# Order339582-10x10-SandyNoble-Polarshield.net
KiCad netlist of a schematic drawn in EAGLE
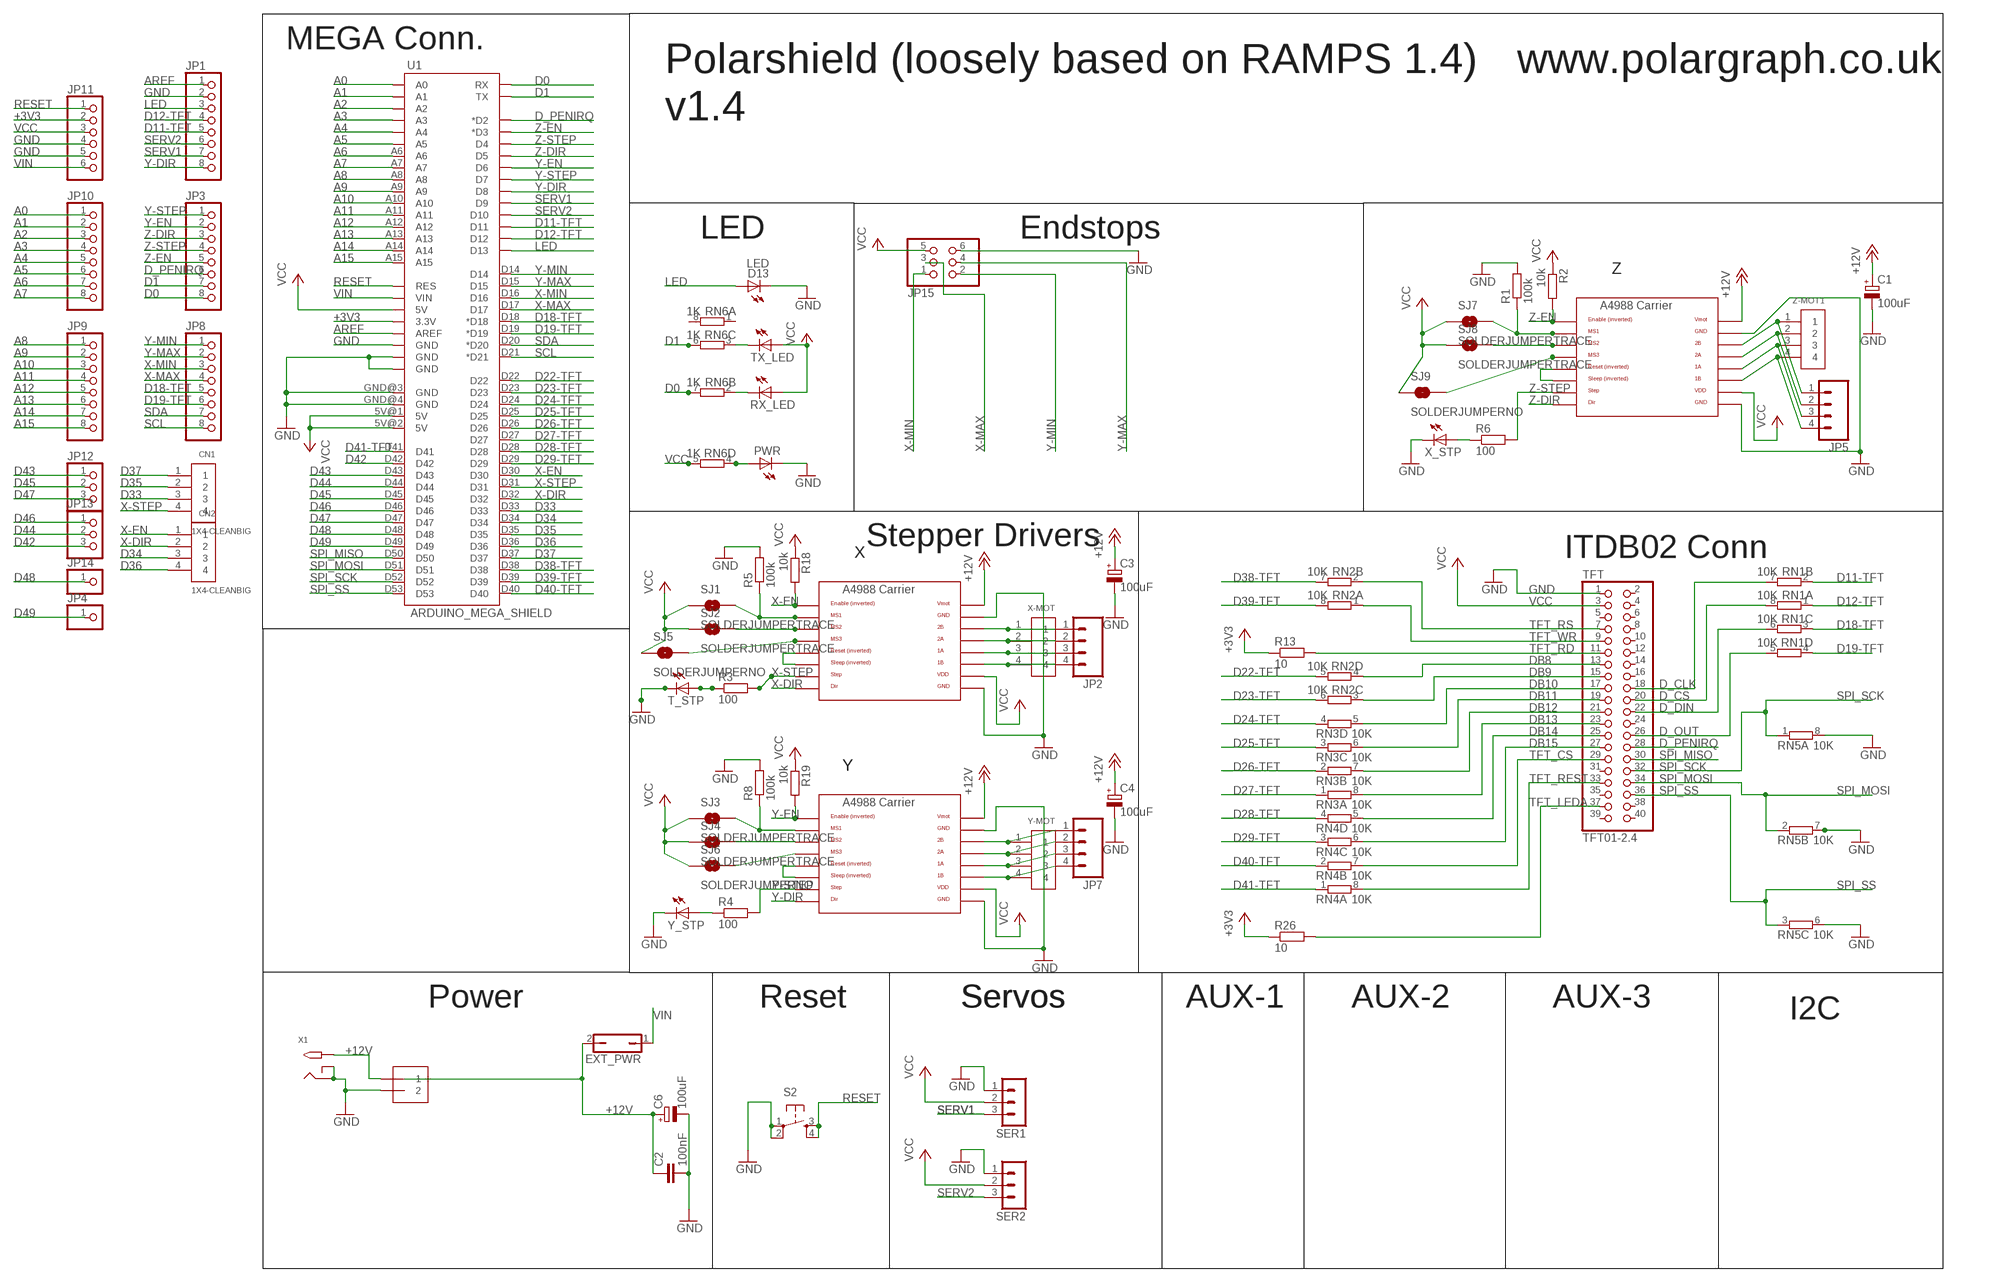
[diagram p0: schematic, sheet 1]

(export (version "E")
  (design (tool "Eeschema 10.0.6"))
  (components
    (comp (ref "C1")
      (value "100uF")
      (footprint "eagle-import:153CLV-0605")
      (libsource (lib "eagle-import") (part "CPOL-EU153CLV-0605"))
    )
    (comp (ref "C2")
      (value "100nF")
      (footprint "eagle-import:C0805")
      (libsource (lib "eagle-import") (part "C-EUC0805"))
    )
    (comp (ref "C3")
      (value "100uF")
      (footprint "eagle-import:153CLV-0605")
      (libsource (lib "eagle-import") (part "CPOL-EU153CLV-0605"))
    )
    (comp (ref "C4")
      (value "100uF")
      (footprint "eagle-import:153CLV-0605")
      (libsource (lib "eagle-import") (part "CPOL-EU153CLV-0605"))
    )
    (comp (ref "C6")
      (value "100uF")
      (footprint "eagle-import:153CLV-0605")
      (libsource (lib "eagle-import") (part "CPOL-EU153CLV-0605"))
    )
    (comp (ref "CN1")
      (value "1X4-CLEANBIG")
      (footprint "eagle-import:1X04-CLEANBIG")
      (libsource (lib "eagle-import") (part "1X4-CLEANBIG"))
    )
    (comp (ref "CN2")
      (value "1X4-CLEANBIG")
      (footprint "eagle-import:1X04-CLEANBIG")
      (libsource (lib "eagle-import") (part "1X4-CLEANBIG"))
    )
    (comp (ref "D13")
      (value "LED")
      (footprint "eagle-import:CHIP-LED0805")
      (libsource (lib "eagle-import") (part "LEDCHIP-LED0805"))
    )
    (comp (ref "EXT_PWR")
      (value "JP1Q")
      (footprint "eagle-import:JP1")
      (libsource (lib "eagle-import") (part "JP1Q"))
    )
    (comp (ref "J1")
      (value "1X2-3.5MM")
      (footprint "eagle-import:1X2-3.5MM")
      (libsource (lib "eagle-import") (part "1X2-3.5MM"))
    )
    (comp (ref "JP1")
      (value "PINHD-1X8CLEANBIG")
      (footprint "eagle-import:1X08-CLEANBIG")
      (libsource (lib "eagle-import") (part "PINHD-1X8CLEANBIG"))
    )
    (comp (ref "JP2")
      (value "M04SCREW")
      (footprint "eagle-import:SCREWTERMINAL-3.5MM-4")
      (libsource (lib "eagle-import") (part "M04SCREW"))
    )
    (comp (ref "JP3")
      (value "PINHD-1X8CLEANBIG")
      (footprint "eagle-import:1X08-CLEANBIG")
      (libsource (lib "eagle-import") (part "PINHD-1X8CLEANBIG"))
    )
    (comp (ref "JP4")
      (value "PINHD-1X1CB")
      (footprint "eagle-import:1X01-CLEANBIG")
      (libsource (lib "eagle-import") (part "PINHD-1X1CB"))
    )
    (comp (ref "JP5")
      (value "M04SCREW")
      (footprint "eagle-import:SCREWTERMINAL-3.5MM-4")
      (libsource (lib "eagle-import") (part "M04SCREW"))
    )
    (comp (ref "JP7")
      (value "M04SCREW")
      (footprint "eagle-import:SCREWTERMINAL-3.5MM-4")
      (libsource (lib "eagle-import") (part "M04SCREW"))
    )
    (comp (ref "JP8")
      (value "PINHD-1X8CLEANBIG")
      (footprint "eagle-import:1X08-CLEANBIG")
      (libsource (lib "eagle-import") (part "PINHD-1X8CLEANBIG"))
    )
    (comp (ref "JP9")
      (value "PINHD-1X8CLEANBIG")
      (footprint "eagle-import:1X08-CLEANBIG")
      (libsource (lib "eagle-import") (part "PINHD-1X8CLEANBIG"))
    )
    (comp (ref "JP10")
      (value "PINHD-1X8CLEANBIG")
      (footprint "eagle-import:1X08-CLEANBIG")
      (libsource (lib "eagle-import") (part "PINHD-1X8CLEANBIG"))
    )
    (comp (ref "JP11")
      (value "PINHD-1X6CB")
      (footprint "eagle-import:1X06-CLEANBIG")
      (libsource (lib "eagle-import") (part "PINHD-1X6CB"))
    )
    (comp (ref "JP12")
      (value "PINHD-1X3CB")
      (footprint "eagle-import:1X03-CLEANBIG")
      (libsource (lib "eagle-import") (part "PINHD-1X3CB"))
    )
    (comp (ref "JP13")
      (value "PINHD-1X3CB")
      (footprint "eagle-import:1X03-CLEANBIG")
      (libsource (lib "eagle-import") (part "PINHD-1X3CB"))
    )
    (comp (ref "JP14")
      (value "PINHD-1X1CB")
      (footprint "eagle-import:1X01-CLEANBIG")
      (libsource (lib "eagle-import") (part "PINHD-1X1CB"))
    )
    (comp (ref "JP15")
      (value "PINHD-2X3")
      (footprint "eagle-import:2X03")
      (libsource (lib "eagle-import") (part "PINHD-2X3"))
    )
    (comp (ref "PWR")
      (value "LEDCHIP-LED0805")
      (footprint "eagle-import:CHIP-LED0805")
      (libsource (lib "eagle-import") (part "LEDCHIP-LED0805"))
    )
    (comp (ref "R1")
      (value "100k")
      (footprint "eagle-import:R0805")
      (libsource (lib "eagle-import") (part "R-EU_R0805"))
    )
    (comp (ref "R2")
      (value "10k")
      (footprint "eagle-import:R0805")
      (libsource (lib "eagle-import") (part "R-EU_R0805"))
    )
    (comp (ref "R3")
      (value "100")
      (footprint "eagle-import:R0805")
      (libsource (lib "eagle-import") (part "R-EU_R0805"))
    )
    (comp (ref "R4")
      (value "100")
      (footprint "eagle-import:R0805")
      (libsource (lib "eagle-import") (part "R-EU_R0805"))
    )
    (comp (ref "R5")
      (value "100k")
      (footprint "eagle-import:R0805")
      (libsource (lib "eagle-import") (part "R-EU_R0805"))
    )
    (comp (ref "R6")
      (value "100")
      (footprint "eagle-import:R0805")
      (libsource (lib "eagle-import") (part "R-EU_R0805"))
    )
    (comp (ref "R8")
      (value "100k")
      (footprint "eagle-import:R0805")
      (libsource (lib "eagle-import") (part "R-EU_R0805"))
    )
    (comp (ref "R13")
      (value "10")
      (footprint "eagle-import:R0805")
      (libsource (lib "eagle-import") (part "resistor_R-EU_R0805"))
    )
    (comp (ref "R18")
      (value "10k")
      (footprint "eagle-import:R0805")
      (libsource (lib "eagle-import") (part "R-EU_R0805"))
    )
    (comp (ref "R19")
      (value "10k")
      (footprint "eagle-import:R0805")
      (libsource (lib "eagle-import") (part "R-EU_R0805"))
    )
    (comp (ref "R26")
      (value "10")
      (footprint "eagle-import:R0805")
      (libsource (lib "eagle-import") (part "resistor_R-EU_R0805"))
    )
    (comp (ref "RN1")
      (value "10K")
      (footprint "eagle-import:EXBS8V")
      (libsource (lib "eagle-import") (part "4R-NEXBS8V"))
    )
    (comp (ref "RN2")
      (value "10K")
      (footprint "eagle-import:EXBS8V")
      (libsource (lib "eagle-import") (part "4R-NEXBS8V"))
    )
    (comp (ref "RN3")
      (value "10K")
      (footprint "eagle-import:EXBS8V")
      (libsource (lib "eagle-import") (part "4R-NEXBS8V"))
    )
    (comp (ref "RN4")
      (value "10K")
      (footprint "eagle-import:EXBS8V")
      (libsource (lib "eagle-import") (part "4R-NEXBS8V"))
    )
    (comp (ref "RN5")
      (value "10K")
      (footprint "eagle-import:EXBS8V")
      (libsource (lib "eagle-import") (part "4R-NEXBS8V"))
    )
    (comp (ref "RN6")
      (value "1K")
      (footprint "eagle-import:EXBS8V")
      (libsource (lib "eagle-import") (part "4R-NEXBS8V"))
    )
    (comp (ref "RX_LED")
      (value "LEDCHIP-LED0805")
      (footprint "eagle-import:CHIP-LED0805")
      (libsource (lib "eagle-import") (part "LEDCHIP-LED0805"))
    )
    (comp (ref "S2")
      (value "TAC_SWITCHPTH")
      (footprint "eagle-import:TACTILE-PTH")
      (libsource (lib "eagle-import") (part "TAC_SWITCHPTH"))
    )
    (comp (ref "SER1")
      (value "3PIN-HEADER")
      (footprint "eagle-import:3PIN-HEADER")
      (libsource (lib "eagle-import") (part "3PIN-HEADER"))
    )
    (comp (ref "SER2")
      (value "3PIN-HEADER")
      (footprint "eagle-import:3PIN-HEADER")
      (libsource (lib "eagle-import") (part "3PIN-HEADER"))
    )
    (comp (ref "SJ1")
      (value "SOLDERJUMPERTRACE")
      (footprint "eagle-import:SJ_2S-TRACE")
      (libsource (lib "eagle-import") (part "SOLDERJUMPERTRACE"))
    )
    (comp (ref "SJ2")
      (value "SOLDERJUMPERTRACE")
      (footprint "eagle-import:SJ_2S-TRACE")
      (libsource (lib "eagle-import") (part "SOLDERJUMPERTRACE"))
    )
    (comp (ref "SJ3")
      (value "SOLDERJUMPERTRACE")
      (footprint "eagle-import:SJ_2S-TRACE")
      (libsource (lib "eagle-import") (part "SOLDERJUMPERTRACE"))
    )
    (comp (ref "SJ4")
      (value "SOLDERJUMPERTRACE")
      (footprint "eagle-import:SJ_2S-TRACE")
      (libsource (lib "eagle-import") (part "SOLDERJUMPERTRACE"))
    )
    (comp (ref "SJ5")
      (value "SOLDERJUMPERNO")
      (footprint "eagle-import:SJ_2S-NO")
      (libsource (lib "eagle-import") (part "SOLDERJUMPERNO"))
    )
    (comp (ref "SJ6")
      (value "SOLDERJUMPERNO")
      (footprint "eagle-import:SJ_2S-NO")
      (libsource (lib "eagle-import") (part "SOLDERJUMPERNO"))
    )
    (comp (ref "SJ7")
      (value "SOLDERJUMPERTRACE")
      (footprint "eagle-import:SJ_2S-TRACE")
      (libsource (lib "eagle-import") (part "SOLDERJUMPERTRACE"))
    )
    (comp (ref "SJ8")
      (value "SOLDERJUMPERTRACE")
      (footprint "eagle-import:SJ_2S-TRACE")
      (libsource (lib "eagle-import") (part "SOLDERJUMPERTRACE"))
    )
    (comp (ref "SJ9")
      (value "SOLDERJUMPERNO")
      (footprint "eagle-import:SJ_2S-NO")
      (libsource (lib "eagle-import") (part "SOLDERJUMPERNO"))
    )
    (comp (ref "TFT")
      (value "TFT01-2.4")
      (footprint "eagle-import:TFT01-2.4")
      (libsource (lib "eagle-import") (part "TFT01-2.4"))
    )
    (comp (ref "TX_LED")
      (value "LEDCHIP-LED0805")
      (footprint "eagle-import:CHIP-LED0805")
      (libsource (lib "eagle-import") (part "LEDCHIP-LED0805"))
    )
    (comp (ref "T_STP")
      (value "LEDCHIP-LED0805")
      (footprint "eagle-import:CHIP-LED0805")
      (libsource (lib "eagle-import") (part "LEDCHIP-LED0805"))
    )
    (comp (ref "U$1")
      (value "A4988BREAKOUT")
      (footprint "eagle-import:A4988BREAKOUT")
      (libsource (lib "eagle-import") (part "A4988BREAKOUT"))
    )
    (comp (ref "U$6")
      (value "A4988BREAKOUT")
      (footprint "eagle-import:A4988BREAKOUT")
      (libsource (lib "eagle-import") (part "A4988BREAKOUT"))
    )
    (comp (ref "U$7")
      (value "A4988BREAKOUT")
      (footprint "eagle-import:A4988BREAKOUT")
      (libsource (lib "eagle-import") (part "A4988BREAKOUT"))
    )
    (comp (ref "U1")
      (value "ARDUINO_MEGA_SHIELD")
      (footprint "eagle-import:ARDUINO_MEGA_SHIELD")
      (libsource (lib "eagle-import") (part "ARDUINO_MEGA_SHIELD"))
    )
    (comp (ref "X-MOT")
      (value "1X4-BIG")
      (footprint "eagle-import:1X04-BIG")
      (libsource (lib "eagle-import") (part "1X4-BIG"))
    )
    (comp (ref "X1")
      (value "2.1MMJACKTHM")
      (footprint "eagle-import:PJ-102A")
      (libsource (lib "eagle-import") (part "2.1MMJACKTHM"))
    )
    (comp (ref "X_STP")
      (value "LEDCHIP-LED0805")
      (footprint "eagle-import:CHIP-LED0805")
      (libsource (lib "eagle-import") (part "LEDCHIP-LED0805"))
    )
    (comp (ref "Y-MOT")
      (value "1X4-BIG")
      (footprint "eagle-import:1X04-BIG")
      (libsource (lib "eagle-import") (part "1X4-BIG"))
    )
    (comp (ref "Y_STP")
      (value "LEDCHIP-LED0805")
      (footprint "eagle-import:CHIP-LED0805")
      (libsource (lib "eagle-import") (part "LEDCHIP-LED0805"))
    )
    (comp (ref "Z-MOT1")
      (value "1X4-BIG")
      (footprint "eagle-import:1X04-BIG")
      (libsource (lib "eagle-import") (part "1X4-BIG"))
    )
  )
  (nets
    (net (code "1") (name "+3V3") (class "Default")
      (node (ref "JP11") (pin "2") (pinfunction "2_2") (pintype "passive"))
      (node (ref "R13") (pin "1") (pinfunction "1_1") (pintype "passive"))
      (node (ref "R26") (pin "1") (pinfunction "1_1") (pintype "passive"))
      (node (ref "U1") (pin "3.3V") (pinfunction "3.3V_3.3V") (pintype "bidirectional"))
    )
    (net (code "2") (name "+12V") (class "Default")
      (node (ref "C1") (pin "+") (pinfunction "+_+") (pintype "passive"))
      (node (ref "C2") (pin "1") (pinfunction "1_1") (pintype "passive"))
      (node (ref "C3") (pin "+") (pinfunction "+_+") (pintype "passive"))
      (node (ref "C4") (pin "+") (pinfunction "+_+") (pintype "passive"))
      (node (ref "C6") (pin "+") (pinfunction "+_+") (pintype "passive"))
      (node (ref "EXT_PWR") (pin "2") (pinfunction "2_2") (pintype "passive"))
      (node (ref "J1") (pin "1") (pinfunction "1_1") (pintype "passive"))
      (node (ref "U$1") (pin "VMOT") (pinfunction "VMOT_VMOT") (pintype "power_in"))
      (node (ref "U$6") (pin "VMOT") (pinfunction "VMOT_VMOT") (pintype "power_in"))
      (node (ref "U$7") (pin "VMOT") (pinfunction "VMOT_VMOT") (pintype "power_in"))
      (node (ref "X1") (pin "TIP") (pinfunction "TIP_TIP") (pintype "bidirectional"))
    )
    (net (code "3") (name "/A0") (class "Default")
      (node (ref "JP10") (pin "1") (pinfunction "1_1") (pintype "passive"))
      (node (ref "U1") (pin "A0") (pinfunction "A0_A0") (pintype "bidirectional"))
    )
    (net (code "4") (name "/A1") (class "Default")
      (node (ref "JP10") (pin "2") (pinfunction "2_2") (pintype "passive"))
      (node (ref "U1") (pin "A1") (pinfunction "A1_A1") (pintype "bidirectional"))
    )
    (net (code "5") (name "/A2") (class "Default")
      (node (ref "JP10") (pin "3") (pinfunction "3_3") (pintype "passive"))
      (node (ref "U1") (pin "A2") (pinfunction "A2_A2") (pintype "bidirectional"))
    )
    (net (code "6") (name "/A3") (class "Default")
      (node (ref "JP10") (pin "4") (pinfunction "4_4") (pintype "passive"))
      (node (ref "U1") (pin "A3") (pinfunction "A3_A3") (pintype "bidirectional"))
    )
    (net (code "7") (name "/A4") (class "Default")
      (node (ref "JP10") (pin "5") (pinfunction "5_5") (pintype "passive"))
      (node (ref "U1") (pin "A4") (pinfunction "A4_A4") (pintype "bidirectional"))
    )
    (net (code "8") (name "/A5") (class "Default")
      (node (ref "JP10") (pin "6") (pinfunction "6_6") (pintype "passive"))
      (node (ref "U1") (pin "A5") (pinfunction "A5_A5") (pintype "bidirectional"))
    )
    (net (code "9") (name "/A6") (class "Default")
      (node (ref "JP10") (pin "7") (pinfunction "7_7") (pintype "passive"))
      (node (ref "U1") (pin "A6") (pinfunction "A6_A6") (pintype "bidirectional"))
    )
    (net (code "10") (name "/A7") (class "Default")
      (node (ref "JP10") (pin "8") (pinfunction "8_8") (pintype "passive"))
      (node (ref "U1") (pin "A7") (pinfunction "A7_A7") (pintype "bidirectional"))
    )
    (net (code "11") (name "/A8") (class "Default")
      (node (ref "JP9") (pin "1") (pinfunction "1_1") (pintype "passive"))
      (node (ref "U1") (pin "A8") (pinfunction "A8_A8") (pintype "bidirectional"))
    )
    (net (code "12") (name "/A9") (class "Default")
      (node (ref "JP9") (pin "2") (pinfunction "2_2") (pintype "passive"))
      (node (ref "U1") (pin "A9") (pinfunction "A9_A9") (pintype "bidirectional"))
    )
    (net (code "13") (name "/A10") (class "Default")
      (node (ref "JP9") (pin "3") (pinfunction "3_3") (pintype "passive"))
      (node (ref "U1") (pin "A10") (pinfunction "A10_A10") (pintype "bidirectional"))
    )
    (net (code "14") (name "/A11") (class "Default")
      (node (ref "JP9") (pin "4") (pinfunction "4_4") (pintype "passive"))
      (node (ref "U1") (pin "A11") (pinfunction "A11_A11") (pintype "bidirectional"))
    )
    (net (code "15") (name "/A12") (class "Default")
      (node (ref "JP9") (pin "5") (pinfunction "5_5") (pintype "passive"))
      (node (ref "U1") (pin "A12") (pinfunction "A12_A12") (pintype "bidirectional"))
    )
    (net (code "16") (name "/A13") (class "Default")
      (node (ref "JP9") (pin "6") (pinfunction "6_6") (pintype "passive"))
      (node (ref "U1") (pin "A13") (pinfunction "A13_A13") (pintype "bidirectional"))
    )
    (net (code "17") (name "/A14") (class "Default")
      (node (ref "JP9") (pin "7") (pinfunction "7_7") (pintype "passive"))
      (node (ref "U1") (pin "A14") (pinfunction "A14_A14") (pintype "bidirectional"))
    )
    (net (code "18") (name "/A15") (class "Default")
      (node (ref "JP9") (pin "8") (pinfunction "8_8") (pintype "passive"))
      (node (ref "U1") (pin "A15") (pinfunction "A15_A15") (pintype "bidirectional"))
    )
    (net (code "19") (name "/AREF") (class "Default")
      (node (ref "JP1") (pin "1") (pinfunction "1_1") (pintype "passive"))
      (node (ref "U1") (pin "AREF") (pinfunction "AREF_AREF") (pintype "bidirectional"))
    )
    (net (code "20") (name "/D0") (class "Default")
      (node (ref "JP3") (pin "8") (pinfunction "8_8") (pintype "passive"))
      (node (ref "RN6") (pin "7") (pinfunction "2_7") (pintype "passive"))
      (node (ref "U1") (pin "RX") (pinfunction "RX_RX") (pintype "bidirectional"))
    )
    (net (code "21") (name "/D1") (class "Default")
      (node (ref "JP3") (pin "7") (pinfunction "7_7") (pintype "passive"))
      (node (ref "RN6") (pin "6") (pinfunction "2_6") (pintype "passive"))
      (node (ref "U1") (pin "TX") (pinfunction "TX_TX") (pintype "bidirectional"))
    )
    (net (code "22") (name "/D11-TFT") (class "Default")
      (node (ref "JP1") (pin "5") (pinfunction "5_5") (pintype "passive"))
      (node (ref "RN1") (pin "2") (pinfunction "1_2") (pintype "passive"))
      (node (ref "U1") (pin "D11") (pinfunction "D11_D11") (pintype "bidirectional"))
    )
    (net (code "23") (name "/D12-TFT") (class "Default")
      (node (ref "JP1") (pin "4") (pinfunction "4_4") (pintype "passive"))
      (node (ref "RN1") (pin "1") (pinfunction "1_1") (pintype "passive"))
      (node (ref "U1") (pin "D12") (pinfunction "D12_D12") (pintype "bidirectional"))
    )
    (net (code "24") (name "/D18-TFT") (class "Default")
      (node (ref "JP8") (pin "5") (pinfunction "5_5") (pintype "passive"))
      (node (ref "RN1") (pin "3") (pinfunction "1_3") (pintype "passive"))
      (node (ref "U1") (pin "D18") (pinfunction "*D18_D18") (pintype "bidirectional"))
    )
    (net (code "25") (name "/D19-TFT") (class "Default")
      (node (ref "JP8") (pin "6") (pinfunction "6_6") (pintype "passive"))
      (node (ref "RN1") (pin "4") (pinfunction "1_4") (pintype "passive"))
      (node (ref "U1") (pin "D19") (pinfunction "*D19_D19") (pintype "bidirectional"))
    )
    (net (code "26") (name "/D22-TFT") (class "Default")
      (node (ref "RN2") (pin "5") (pinfunction "2_5") (pintype "passive"))
      (node (ref "U1") (pin "D22") (pinfunction "D22_D22") (pintype "bidirectional"))
    )
    (net (code "27") (name "/D23-TFT") (class "Default")
      (node (ref "RN2") (pin "6") (pinfunction "2_6") (pintype "passive"))
      (node (ref "U1") (pin "D23") (pinfunction "D23_D23") (pintype "bidirectional"))
    )
    (net (code "28") (name "/D24-TFT") (class "Default")
      (node (ref "RN3") (pin "4") (pinfunction "1_4") (pintype "passive"))
      (node (ref "U1") (pin "D24") (pinfunction "D24_D24") (pintype "bidirectional"))
    )
    (net (code "29") (name "/D25-TFT") (class "Default")
      (node (ref "RN3") (pin "3") (pinfunction "1_3") (pintype "passive"))
      (node (ref "U1") (pin "D25") (pinfunction "D25_D25") (pintype "bidirectional"))
    )
    (net (code "30") (name "/D26-TFT") (class "Default")
      (node (ref "RN3") (pin "2") (pinfunction "1_2") (pintype "passive"))
      (node (ref "U1") (pin "D26") (pinfunction "D26_D26") (pintype "bidirectional"))
    )
    (net (code "31") (name "/D27-TFT") (class "Default")
      (node (ref "RN3") (pin "1") (pinfunction "1_1") (pintype "passive"))
      (node (ref "U1") (pin "D27") (pinfunction "D27_D27") (pintype "bidirectional"))
    )
    (net (code "32") (name "/D28-TFT") (class "Default")
      (node (ref "RN4") (pin "4") (pinfunction "1_4") (pintype "passive"))
      (node (ref "U1") (pin "D28") (pinfunction "D28_D28") (pintype "bidirectional"))
    )
    (net (code "33") (name "/D29-TFT") (class "Default")
      (node (ref "RN4") (pin "3") (pinfunction "1_3") (pintype "passive"))
      (node (ref "U1") (pin "D29") (pinfunction "D29_D29") (pintype "bidirectional"))
    )
    (net (code "34") (name "/D33") (class "Default")
      (node (ref "CN1") (pin "3") (pinfunction "3_3") (pintype "bidirectional"))
      (node (ref "U1") (pin "D33") (pinfunction "D33_D33") (pintype "bidirectional"))
    )
    (net (code "35") (name "/D34") (class "Default")
      (node (ref "CN2") (pin "3") (pinfunction "3_3") (pintype "bidirectional"))
      (node (ref "U1") (pin "D34") (pinfunction "D34_D34") (pintype "bidirectional"))
    )
    (net (code "36") (name "/D35") (class "Default")
      (node (ref "CN1") (pin "2") (pinfunction "2_2") (pintype "bidirectional"))
      (node (ref "U1") (pin "D35") (pinfunction "D35_D35") (pintype "bidirectional"))
    )
    (net (code "37") (name "/D36") (class "Default")
      (node (ref "CN2") (pin "4") (pinfunction "4_4") (pintype "bidirectional"))
      (node (ref "U1") (pin "D36") (pinfunction "D36_D36") (pintype "bidirectional"))
    )
    (net (code "38") (name "/D37") (class "Default")
      (node (ref "CN1") (pin "1") (pinfunction "1_1") (pintype "bidirectional"))
      (node (ref "U1") (pin "D37") (pinfunction "D37_D37") (pintype "bidirectional"))
    )
    (net (code "39") (name "/D38-TFT") (class "Default")
      (node (ref "RN2") (pin "7") (pinfunction "2_7") (pintype "passive"))
      (node (ref "U1") (pin "D38") (pinfunction "D38_D38") (pintype "bidirectional"))
    )
    (net (code "40") (name "/D39-TFT") (class "Default")
      (node (ref "RN2") (pin "8") (pinfunction "2_8") (pintype "passive"))
      (node (ref "U1") (pin "D39") (pinfunction "D39_D39") (pintype "bidirectional"))
    )
    (net (code "41") (name "/D40-TFT") (class "Default")
      (node (ref "RN4") (pin "2") (pinfunction "1_2") (pintype "passive"))
      (node (ref "U1") (pin "D40") (pinfunction "D40_D40") (pintype "bidirectional"))
    )
    (net (code "42") (name "/D41-TFT") (class "Default")
      (node (ref "RN4") (pin "1") (pinfunction "1_1") (pintype "passive"))
      (node (ref "U1") (pin "D41") (pinfunction "D41_D41") (pintype "bidirectional"))
    )
    (net (code "43") (name "/D42") (class "Default")
      (node (ref "JP13") (pin "3") (pinfunction "3_3") (pintype "passive"))
      (node (ref "U1") (pin "D42") (pinfunction "D42_D42") (pintype "bidirectional"))
    )
    (net (code "44") (name "/D43") (class "Default")
      (node (ref "JP12") (pin "1") (pinfunction "1_1") (pintype "passive"))
      (node (ref "U1") (pin "D43") (pinfunction "D43_D43") (pintype "bidirectional"))
    )
    (net (code "45") (name "/D44") (class "Default")
      (node (ref "JP13") (pin "2") (pinfunction "2_2") (pintype "passive"))
      (node (ref "U1") (pin "D44") (pinfunction "D44_D44") (pintype "bidirectional"))
    )
    (net (code "46") (name "/D45") (class "Default")
      (node (ref "JP12") (pin "2") (pinfunction "2_2") (pintype "passive"))
      (node (ref "U1") (pin "D45") (pinfunction "D45_D45") (pintype "bidirectional"))
    )
    (net (code "47") (name "/D46") (class "Default")
      (node (ref "JP13") (pin "1") (pinfunction "1_1") (pintype "passive"))
      (node (ref "U1") (pin "D46") (pinfunction "D46_D46") (pintype "bidirectional"))
    )
    (net (code "48") (name "/D47") (class "Default")
      (node (ref "JP12") (pin "3") (pinfunction "3_3") (pintype "passive"))
      (node (ref "U1") (pin "D47") (pinfunction "D47_D47") (pintype "bidirectional"))
    )
    (net (code "49") (name "/D48") (class "Default")
      (node (ref "JP14") (pin "1") (pinfunction "1_1") (pintype "passive"))
      (node (ref "U1") (pin "D48") (pinfunction "D48_D48") (pintype "bidirectional"))
    )
    (net (code "50") (name "/D49") (class "Default")
      (node (ref "JP4") (pin "1") (pinfunction "1_1") (pintype "passive"))
      (node (ref "U1") (pin "D49") (pinfunction "D49_D49") (pintype "bidirectional"))
    )
    (net (code "51") (name "/DB8") (class "Default")
      (node (ref "RN2") (pin "4") (pinfunction "1_4") (pintype "passive"))
      (node (ref "TFT") (pin "13") (pinfunction "13_13") (pintype "passive"))
    )
    (net (code "52") (name "/DB9") (class "Default")
      (node (ref "RN2") (pin "3") (pinfunction "1_3") (pintype "passive"))
      (node (ref "TFT") (pin "15") (pinfunction "15_15") (pintype "passive"))
    )
    (net (code "53") (name "/DB10") (class "Default")
      (node (ref "RN3") (pin "5") (pinfunction "2_5") (pintype "passive"))
      (node (ref "TFT") (pin "17") (pinfunction "17_17") (pintype "passive"))
    )
    (net (code "54") (name "/DB11") (class "Default")
      (node (ref "RN3") (pin "6") (pinfunction "2_6") (pintype "passive"))
      (node (ref "TFT") (pin "19") (pinfunction "19_19") (pintype "passive"))
    )
    (net (code "55") (name "/DB12") (class "Default")
      (node (ref "RN3") (pin "7") (pinfunction "2_7") (pintype "passive"))
      (node (ref "TFT") (pin "21") (pinfunction "21_21") (pintype "passive"))
    )
    (net (code "56") (name "/DB13") (class "Default")
      (node (ref "RN3") (pin "8") (pinfunction "2_8") (pintype "passive"))
      (node (ref "TFT") (pin "23") (pinfunction "23_23") (pintype "passive"))
    )
    (net (code "57") (name "/DB14") (class "Default")
      (node (ref "RN4") (pin "5") (pinfunction "2_5") (pintype "passive"))
      (node (ref "TFT") (pin "25") (pinfunction "25_25") (pintype "passive"))
    )
    (net (code "58") (name "/DB15") (class "Default")
      (node (ref "RN4") (pin "6") (pinfunction "2_6") (pintype "passive"))
      (node (ref "TFT") (pin "27") (pinfunction "27_27") (pintype "passive"))
    )
    (net (code "59") (name "/D_CLK") (class "Default")
      (node (ref "RN1") (pin "7") (pinfunction "2_7") (pintype "passive"))
      (node (ref "TFT") (pin "18") (pinfunction "18_18") (pintype "passive"))
    )
    (net (code "60") (name "/D_CS") (class "Default")
      (node (ref "RN1") (pin "8") (pinfunction "2_8") (pintype "passive"))
      (node (ref "TFT") (pin "20") (pinfunction "20_20") (pintype "passive"))
    )
    (net (code "61") (name "/D_DIN") (class "Default")
      (node (ref "RN1") (pin "6") (pinfunction "2_6") (pintype "passive"))
      (node (ref "TFT") (pin "22") (pinfunction "22_22") (pintype "passive"))
    )
    (net (code "62") (name "/D_OUT") (class "Default")
      (node (ref "RN1") (pin "5") (pinfunction "2_5") (pintype "passive"))
      (node (ref "TFT") (pin "26") (pinfunction "26_26") (pintype "passive"))
    )
    (net (code "63") (name "/D_PENIRQ") (class "Default")
      (node (ref "JP3") (pin "6") (pinfunction "6_6") (pintype "passive"))
      (node (ref "TFT") (pin "28") (pinfunction "28_28") (pintype "passive"))
      (node (ref "U1") (pin "D2") (pinfunction "*D2_D2") (pintype "bidirectional"))
    )
    (net (code "64") (name "/LED") (class "Default")
      (node (ref "D13") (pin "A") (pinfunction "A_A") (pintype "passive"))
      (node (ref "JP1") (pin "3") (pinfunction "3_3") (pintype "passive"))
      (node (ref "U1") (pin "D13") (pinfunction "D13_D13") (pintype "bidirectional"))
    )
    (net (code "65") (name "/RESET") (class "Default")
      (node (ref "JP11") (pin "1") (pinfunction "1_1") (pintype "passive"))
      (node (ref "S2") (pin "3") (pinfunction "3_3") (pintype "passive"))
      (node (ref "S2") (pin "4") (pinfunction "4_4") (pintype "passive"))
      (node (ref "U1") (pin "RES") (pinfunction "RES_RES") (pintype "bidirectional"))
    )
    (net (code "66") (name "/SCL") (class "Default")
      (node (ref "JP8") (pin "8") (pinfunction "8_8") (pintype "passive"))
      (node (ref "U1") (pin "D21") (pinfunction "*D21_D21") (pintype "bidirectional"))
    )
    (net (code "67") (name "/SDA") (class "Default")
      (node (ref "JP8") (pin "7") (pinfunction "7_7") (pintype "passive"))
      (node (ref "U1") (pin "D20") (pinfunction "*D20_D20") (pintype "bidirectional"))
    )
    (net (code "68") (name "/SERV1") (class "Default")
      (node (ref "JP1") (pin "7") (pinfunction "7_7") (pintype "passive"))
      (node (ref "SER1") (pin "3") (pinfunction "3_3") (pintype "passive"))
      (node (ref "U1") (pin "D9") (pinfunction "D9_D9") (pintype "bidirectional"))
    )
    (net (code "69") (name "/SERV2") (class "Default")
      (node (ref "JP1") (pin "6") (pinfunction "6_6") (pintype "passive"))
      (node (ref "SER2") (pin "3") (pinfunction "3_3") (pintype "passive"))
      (node (ref "U1") (pin "D10") (pinfunction "D10_D10") (pintype "bidirectional"))
    )
    (net (code "70") (name "/SPI_MISO") (class "Default")
      (node (ref "TFT") (pin "30") (pinfunction "30_30") (pintype "passive"))
      (node (ref "U1") (pin "D50") (pinfunction "D50_D50") (pintype "bidirectional"))
    )
    (net (code "71") (name "/SPI_MOSI") (class "Default")
      (node (ref "RN5") (pin "2") (pinfunction "1_2") (pintype "passive"))
      (node (ref "TFT") (pin "34") (pinfunction "34_34") (pintype "passive"))
      (node (ref "U1") (pin "D51") (pinfunction "D51_D51") (pintype "bidirectional"))
    )
    (net (code "72") (name "/SPI_SCK") (class "Default")
      (node (ref "RN5") (pin "1") (pinfunction "1_1") (pintype "passive"))
      (node (ref "TFT") (pin "32") (pinfunction "32_32") (pintype "passive"))
      (node (ref "U1") (pin "D52") (pinfunction "D52_D52") (pintype "bidirectional"))
    )
    (net (code "73") (name "/SPI_SS") (class "Default")
      (node (ref "RN5") (pin "3") (pinfunction "1_3") (pintype "passive"))
      (node (ref "TFT") (pin "36") (pinfunction "36_36") (pintype "passive"))
      (node (ref "U1") (pin "D53") (pinfunction "D53_D53") (pintype "bidirectional"))
    )
    (net (code "74") (name "/TFT_CS") (class "Default")
      (node (ref "RN4") (pin "7") (pinfunction "2_7") (pintype "passive"))
      (node (ref "TFT") (pin "29") (pinfunction "29_29") (pintype "passive"))
    )
    (net (code "75") (name "/TFT_LEDA") (class "Default")
      (node (ref "R26") (pin "2") (pinfunction "2_2") (pintype "passive"))
      (node (ref "TFT") (pin "37") (pinfunction "37_37") (pintype "passive"))
    )
    (net (code "76") (name "/TFT_RD") (class "Default")
      (node (ref "R13") (pin "2") (pinfunction "2_2") (pintype "passive"))
      (node (ref "TFT") (pin "11") (pinfunction "11_11") (pintype "passive"))
    )
    (net (code "77") (name "/TFT_REST") (class "Default")
      (node (ref "RN4") (pin "8") (pinfunction "2_8") (pintype "passive"))
      (node (ref "TFT") (pin "33") (pinfunction "33_33") (pintype "passive"))
    )
    (net (code "78") (name "/TFT_RS") (class "Default")
      (node (ref "RN2") (pin "2") (pinfunction "1_2") (pintype "passive"))
      (node (ref "TFT") (pin "7") (pinfunction "7_7") (pintype "passive"))
    )
    (net (code "79") (name "/TFT_WR") (class "Default")
      (node (ref "RN2") (pin "1") (pinfunction "1_1") (pintype "passive"))
      (node (ref "TFT") (pin "9") (pinfunction "9_9") (pintype "passive"))
    )
    (net (code "80") (name "/VIN") (class "Default")
      (node (ref "EXT_PWR") (pin "1") (pinfunction "1_1") (pintype "passive"))
      (node (ref "JP11") (pin "6") (pinfunction "6_6") (pintype "passive"))
      (node (ref "U1") (pin "VIN") (pinfunction "VIN_VIN") (pintype "bidirectional"))
    )
    (net (code "81") (name "/X-DIR") (class "Default")
      (node (ref "CN2") (pin "2") (pinfunction "2_2") (pintype "bidirectional"))
      (node (ref "U$6") (pin "DIR") (pinfunction "DIR_DIR") (pintype "input"))
      (node (ref "U1") (pin "D32") (pinfunction "D32_D32") (pintype "bidirectional"))
    )
    (net (code "82") (name "/X-EN") (class "Default")
      (node (ref "CN2") (pin "1") (pinfunction "1_1") (pintype "bidirectional"))
      (node (ref "R18") (pin "2") (pinfunction "2_2") (pintype "passive"))
      (node (ref "U$6") (pin "EN") (pinfunction "EN_EN") (pintype "input"))
      (node (ref "U1") (pin "D30") (pinfunction "D30_D30") (pintype "bidirectional"))
    )
    (net (code "83") (name "/X-MAX") (class "Default")
      (node (ref "JP15") (pin "3") (pinfunction "3_3") (pintype "passive"))
      (node (ref "JP8") (pin "4") (pinfunction "4_4") (pintype "passive"))
      (node (ref "U1") (pin "D17") (pinfunction "D17_D17") (pintype "bidirectional"))
    )
    (net (code "84") (name "/X-MIN") (class "Default")
      (node (ref "JP15") (pin "1") (pinfunction "1_1") (pintype "passive"))
      (node (ref "JP8") (pin "3") (pinfunction "3_3") (pintype "passive"))
      (node (ref "U1") (pin "D16") (pinfunction "D16_D16") (pintype "bidirectional"))
    )
    (net (code "85") (name "/X-STEP") (class "Default")
      (node (ref "CN1") (pin "4") (pinfunction "4_4") (pintype "bidirectional"))
      (node (ref "R3") (pin "2") (pinfunction "2_2") (pintype "passive"))
      (node (ref "U$6") (pin "STEP") (pinfunction "STEP_STEP") (pintype "input"))
      (node (ref "U1") (pin "D31") (pinfunction "D31_D31") (pintype "bidirectional"))
    )
    (net (code "86") (name "/Y-DIR") (class "Default")
      (node (ref "JP1") (pin "8") (pinfunction "8_8") (pintype "passive"))
      (node (ref "U$7") (pin "DIR") (pinfunction "DIR_DIR") (pintype "input"))
      (node (ref "U1") (pin "D8") (pinfunction "D8_D8") (pintype "bidirectional"))
    )
    (net (code "87") (name "/Y-EN") (class "Default")
      (node (ref "JP3") (pin "2") (pinfunction "2_2") (pintype "passive"))
      (node (ref "R19") (pin "2") (pinfunction "2_2") (pintype "passive"))
      (node (ref "U$7") (pin "EN") (pinfunction "EN_EN") (pintype "input"))
      (node (ref "U1") (pin "D6") (pinfunction "D6_D6") (pintype "bidirectional"))
    )
    (net (code "88") (name "/Y-MAX") (class "Default")
      (node (ref "JP15") (pin "4") (pinfunction "4_4") (pintype "passive"))
      (node (ref "JP8") (pin "2") (pinfunction "2_2") (pintype "passive"))
      (node (ref "U1") (pin "D15") (pinfunction "D15_D15") (pintype "bidirectional"))
    )
    (net (code "89") (name "/Y-MIN") (class "Default")
      (node (ref "JP15") (pin "2") (pinfunction "2_2") (pintype "passive"))
      (node (ref "JP8") (pin "1") (pinfunction "1_1") (pintype "passive"))
      (node (ref "U1") (pin "D14") (pinfunction "D14_D14") (pintype "bidirectional"))
    )
    (net (code "90") (name "/Y-STEP") (class "Default")
      (node (ref "JP3") (pin "1") (pinfunction "1_1") (pintype "passive"))
      (node (ref "R4") (pin "2") (pinfunction "2_2") (pintype "passive"))
      (node (ref "U$7") (pin "STEP") (pinfunction "STEP_STEP") (pintype "input"))
      (node (ref "U1") (pin "D7") (pinfunction "D7_D7") (pintype "bidirectional"))
    )
    (net (code "91") (name "/Z-DIR") (class "Default")
      (node (ref "JP3") (pin "3") (pinfunction "3_3") (pintype "passive"))
      (node (ref "U$1") (pin "DIR") (pinfunction "DIR_DIR") (pintype "input"))
      (node (ref "U1") (pin "D5") (pinfunction "D5_D5") (pintype "bidirectional"))
    )
    (net (code "92") (name "/Z-EN") (class "Default")
      (node (ref "JP3") (pin "5") (pinfunction "5_5") (pintype "passive"))
      (node (ref "R2") (pin "2") (pinfunction "2_2") (pintype "passive"))
      (node (ref "U$1") (pin "EN") (pinfunction "EN_EN") (pintype "input"))
      (node (ref "U1") (pin "D3") (pinfunction "*D3_D3") (pintype "bidirectional"))
    )
    (net (code "93") (name "/Z-STEP") (class "Default")
      (node (ref "JP3") (pin "4") (pinfunction "4_4") (pintype "passive"))
      (node (ref "R6") (pin "2") (pinfunction "2_2") (pintype "passive"))
      (node (ref "U$1") (pin "STEP") (pinfunction "STEP_STEP") (pintype "input"))
      (node (ref "U1") (pin "D4") (pinfunction "D4_D4") (pintype "bidirectional"))
    )
    (net (code "94") (name "GND") (class "Default")
      (node (ref "C1") (pin "-") (pinfunction "-_-") (pintype "passive"))
      (node (ref "C2") (pin "2") (pinfunction "2_2") (pintype "passive"))
      (node (ref "C3") (pin "-") (pinfunction "-_-") (pintype "passive"))
      (node (ref "C4") (pin "-") (pinfunction "-_-") (pintype "passive"))
      (node (ref "C6") (pin "-") (pinfunction "-_-") (pintype "passive"))
      (node (ref "D13") (pin "C") (pinfunction "C_C") (pintype "passive"))
      (node (ref "J1") (pin "2") (pinfunction "2_2") (pintype "passive"))
      (node (ref "JP1") (pin "2") (pinfunction "2_2") (pintype "passive"))
      (node (ref "JP11") (pin "4") (pinfunction "4_4") (pintype "passive"))
      (node (ref "JP11") (pin "5") (pinfunction "5_5") (pintype "passive"))
      (node (ref "JP15") (pin "6") (pinfunction "6_6") (pintype "passive"))
      (node (ref "PWR") (pin "C") (pinfunction "C_C") (pintype "passive"))
      (node (ref "R1") (pin "2") (pinfunction "2_2") (pintype "passive"))
      (node (ref "R5") (pin "2") (pinfunction "2_2") (pintype "passive"))
      (node (ref "R8") (pin "2") (pinfunction "2_2") (pintype "passive"))
      (node (ref "RN5") (pin "6") (pinfunction "2_6") (pintype "passive"))
      (node (ref "RN5") (pin "7") (pinfunction "2_7") (pintype "passive"))
      (node (ref "RN5") (pin "8") (pinfunction "2_8") (pintype "passive"))
      (node (ref "S2") (pin "1") (pinfunction "1_1") (pintype "passive"))
      (node (ref "S2") (pin "2") (pinfunction "2_2") (pintype "passive"))
      (node (ref "SER1") (pin "1") (pinfunction "1_1") (pintype "passive"))
      (node (ref "SER2") (pin "1") (pinfunction "1_1") (pintype "passive"))
      (node (ref "TFT") (pin "1") (pinfunction "1_1") (pintype "passive"))
      (node (ref "T_STP") (pin "C") (pinfunction "C_C") (pintype "passive"))
      (node (ref "U$1") (pin "GND") (pinfunction "GND_GND") (pintype "power_in"))
      (node (ref "U$1") (pin "GND@0") (pinfunction "GND_GND@0") (pintype "power_in"))
      (node (ref "U$6") (pin "GND") (pinfunction "GND_GND") (pintype "power_in"))
      (node (ref "U$6") (pin "GND@0") (pinfunction "GND_GND@0") (pintype "power_in"))
      (node (ref "U$7") (pin "GND") (pinfunction "GND_GND") (pintype "power_in"))
      (node (ref "U$7") (pin "GND@0") (pinfunction "GND_GND@0") (pintype "power_in"))
      (node (ref "U1") (pin "GND@0") (pinfunction "GND_GND@0") (pintype "power_in"))
      (node (ref "U1") (pin "GND@1") (pinfunction "GND_GND@1") (pintype "power_in"))
      (node (ref "U1") (pin "GND@2") (pinfunction "GND_GND@2") (pintype "power_in"))
      (node (ref "U1") (pin "GND@3") (pinfunction "GND_GND@3") (pintype "power_in"))
      (node (ref "U1") (pin "GND@4") (pinfunction "GND_GND@4") (pintype "power_in"))
      (node (ref "X1") (pin "RING") (pinfunction "RING_RING") (pintype "bidirectional"))
      (node (ref "X1") (pin "RING_SW") (pinfunction "RING_SW_RING_SW") (pintype "bidirectional"))
      (node (ref "X_STP") (pin "C") (pinfunction "C_C") (pintype "passive"))
      (node (ref "Y_STP") (pin "C") (pinfunction "C_C") (pintype "passive"))
    )
    (net (code "95") (name "Net-(JP2-Pad1)") (class "Default")
      (node (ref "JP2") (pin "1") (pinfunction "1_1") (pintype "passive"))
      (node (ref "U$6") (pin "2B") (pinfunction "2B_2B") (pintype "output"))
      (node (ref "X-MOT") (pin "1") (pinfunction "1_1") (pintype "bidirectional"))
    )
    (net (code "96") (name "Net-(JP2-Pad2)") (class "Default")
      (node (ref "JP2") (pin "2") (pinfunction "2_2") (pintype "passive"))
      (node (ref "U$6") (pin "2A") (pinfunction "2A_2A") (pintype "output"))
      (node (ref "X-MOT") (pin "2") (pinfunction "2_2") (pintype "bidirectional"))
    )
    (net (code "97") (name "Net-(JP2-Pad3)") (class "Default")
      (node (ref "JP2") (pin "3") (pinfunction "3_3") (pintype "passive"))
      (node (ref "U$6") (pin "1A") (pinfunction "1A_1A") (pintype "output"))
      (node (ref "X-MOT") (pin "3") (pinfunction "3_3") (pintype "bidirectional"))
    )
    (net (code "98") (name "Net-(JP2-Pad4)") (class "Default")
      (node (ref "JP2") (pin "4") (pinfunction "4_4") (pintype "passive"))
      (node (ref "U$6") (pin "1B") (pinfunction "1B_1B") (pintype "output"))
      (node (ref "X-MOT") (pin "4") (pinfunction "4_4") (pintype "bidirectional"))
    )
    (net (code "99") (name "Net-(JP5-Pad1)") (class "Default")
      (node (ref "JP5") (pin "1") (pinfunction "1_1") (pintype "passive"))
      (node (ref "U$1") (pin "2B") (pinfunction "2B_2B") (pintype "output"))
      (node (ref "Z-MOT1") (pin "1") (pinfunction "1_1") (pintype "bidirectional"))
    )
    (net (code "100") (name "Net-(JP5-Pad2)") (class "Default")
      (node (ref "JP5") (pin "2") (pinfunction "2_2") (pintype "passive"))
      (node (ref "U$1") (pin "2A") (pinfunction "2A_2A") (pintype "output"))
      (node (ref "Z-MOT1") (pin "2") (pinfunction "2_2") (pintype "bidirectional"))
    )
    (net (code "101") (name "Net-(JP5-Pad3)") (class "Default")
      (node (ref "JP5") (pin "3") (pinfunction "3_3") (pintype "passive"))
      (node (ref "U$1") (pin "1A") (pinfunction "1A_1A") (pintype "output"))
      (node (ref "Z-MOT1") (pin "3") (pinfunction "3_3") (pintype "bidirectional"))
    )
    (net (code "102") (name "Net-(JP5-Pad4)") (class "Default")
      (node (ref "JP5") (pin "4") (pinfunction "4_4") (pintype "passive"))
      (node (ref "U$1") (pin "1B") (pinfunction "1B_1B") (pintype "output"))
      (node (ref "Z-MOT1") (pin "4") (pinfunction "4_4") (pintype "bidirectional"))
    )
    (net (code "103") (name "Net-(JP7-Pad1)") (class "Default")
      (node (ref "JP7") (pin "1") (pinfunction "1_1") (pintype "passive"))
      (node (ref "U$7") (pin "2B") (pinfunction "2B_2B") (pintype "output"))
      (node (ref "Y-MOT") (pin "1") (pinfunction "1_1") (pintype "bidirectional"))
    )
    (net (code "104") (name "Net-(JP7-Pad2)") (class "Default")
      (node (ref "JP7") (pin "2") (pinfunction "2_2") (pintype "passive"))
      (node (ref "U$7") (pin "2A") (pinfunction "2A_2A") (pintype "output"))
      (node (ref "Y-MOT") (pin "2") (pinfunction "2_2") (pintype "bidirectional"))
    )
    (net (code "105") (name "Net-(JP7-Pad3)") (class "Default")
      (node (ref "JP7") (pin "3") (pinfunction "3_3") (pintype "passive"))
      (node (ref "U$7") (pin "1A") (pinfunction "1A_1A") (pintype "output"))
      (node (ref "Y-MOT") (pin "3") (pinfunction "3_3") (pintype "bidirectional"))
    )
    (net (code "106") (name "Net-(JP7-Pad4)") (class "Default")
      (node (ref "JP7") (pin "4") (pinfunction "4_4") (pintype "passive"))
      (node (ref "U$7") (pin "1B") (pinfunction "1B_1B") (pintype "output"))
      (node (ref "Y-MOT") (pin "4") (pinfunction "4_4") (pintype "bidirectional"))
    )
    (net (code "107") (name "Net-(R1-Pad1)") (class "Default")
      (node (ref "R1") (pin "1") (pinfunction "1_1") (pintype "passive"))
      (node (ref "SJ7") (pin "2") (pinfunction "2_2") (pintype "passive"))
      (node (ref "U$1") (pin "MS1") (pinfunction "MS1_MS1") (pintype "input"))
    )
    (net (code "108") (name "Net-(R3-Pad1)") (class "Default")
      (node (ref "R3") (pin "1") (pinfunction "1_1") (pintype "passive"))
      (node (ref "T_STP") (pin "A") (pinfunction "A_A") (pintype "passive"))
    )
    (net (code "109") (name "Net-(R4-Pad1)") (class "Default")
      (node (ref "R4") (pin "1") (pinfunction "1_1") (pintype "passive"))
      (node (ref "Y_STP") (pin "A") (pinfunction "A_A") (pintype "passive"))
    )
    (net (code "110") (name "Net-(R5-Pad1)") (class "Default")
      (node (ref "R5") (pin "1") (pinfunction "1_1") (pintype "passive"))
      (node (ref "SJ1") (pin "2") (pinfunction "2_2") (pintype "passive"))
      (node (ref "U$6") (pin "MS1") (pinfunction "MS1_MS1") (pintype "input"))
    )
    (net (code "111") (name "Net-(R6-Pad1)") (class "Default")
      (node (ref "R6") (pin "1") (pinfunction "1_1") (pintype "passive"))
      (node (ref "X_STP") (pin "A") (pinfunction "A_A") (pintype "passive"))
    )
    (net (code "112") (name "Net-(R8-Pad1)") (class "Default")
      (node (ref "R8") (pin "1") (pinfunction "1_1") (pintype "passive"))
      (node (ref "SJ3") (pin "2") (pinfunction "2_2") (pintype "passive"))
      (node (ref "U$7") (pin "MS1") (pinfunction "MS1_MS1") (pintype "input"))
    )
    (net (code "113") (name "Net-(RN6B-1)") (class "Default")
      (node (ref "RN6") (pin "2") (pinfunction "1_2") (pintype "passive"))
      (node (ref "RX_LED") (pin "C") (pinfunction "C_C") (pintype "passive"))
    )
    (net (code "114") (name "Net-(RN6C-1)") (class "Default")
      (node (ref "RN6") (pin "3") (pinfunction "1_3") (pintype "passive"))
      (node (ref "TX_LED") (pin "C") (pinfunction "C_C") (pintype "passive"))
    )
    (net (code "115") (name "Net-(RN6D-1)") (class "Default")
      (node (ref "PWR") (pin "A") (pinfunction "A_A") (pintype "passive"))
      (node (ref "RN6") (pin "4") (pinfunction "1_4") (pintype "passive"))
    )
    (net (code "116") (name "Net-(SJ2-Pad2)") (class "Default")
      (node (ref "SJ2") (pin "2") (pinfunction "2_2") (pintype "passive"))
      (node (ref "U$6") (pin "MS2") (pinfunction "MS2_MS2") (pintype "input"))
    )
    (net (code "117") (name "Net-(SJ4-Pad2)") (class "Default")
      (node (ref "SJ4") (pin "2") (pinfunction "2_2") (pintype "passive"))
      (node (ref "U$7") (pin "MS2") (pinfunction "MS2_MS2") (pintype "input"))
    )
    (net (code "118") (name "Net-(SJ5-Pad2)") (class "Default")
      (node (ref "SJ5") (pin "2") (pinfunction "2_2") (pintype "passive"))
      (node (ref "U$6") (pin "MS3") (pinfunction "MS3_MS3") (pintype "input"))
    )
    (net (code "119") (name "Net-(SJ6-Pad2)") (class "Default")
      (node (ref "SJ6") (pin "2") (pinfunction "2_2") (pintype "passive"))
      (node (ref "U$7") (pin "MS3") (pinfunction "MS3_MS3") (pintype "input"))
    )
    (net (code "120") (name "Net-(SJ8-Pad2)") (class "Default")
      (node (ref "SJ8") (pin "2") (pinfunction "2_2") (pintype "passive"))
      (node (ref "U$1") (pin "MS2") (pinfunction "MS2_MS2") (pintype "input"))
    )
    (net (code "121") (name "Net-(SJ9-Pad2)") (class "Default")
      (node (ref "SJ9") (pin "2") (pinfunction "2_2") (pintype "passive"))
      (node (ref "U$1") (pin "MS3") (pinfunction "MS3_MS3") (pintype "input"))
    )
    (net (code "122") (name "Net-(U$1-SLEEP)") (class "Default")
      (node (ref "U$1") (pin "RST") (pinfunction "RST_RST") (pintype "input"))
      (node (ref "U$1") (pin "SLP") (pinfunction "SLEEP_SLP") (pintype "input"))
    )
    (net (code "123") (name "Net-(U$6-SLEEP)") (class "Default")
      (node (ref "U$6") (pin "RST") (pinfunction "RST_RST") (pintype "input"))
      (node (ref "U$6") (pin "SLP") (pinfunction "SLEEP_SLP") (pintype "input"))
    )
    (net (code "124") (name "Net-(U$7-SLEEP)") (class "Default")
      (node (ref "U$7") (pin "RST") (pinfunction "RST_RST") (pintype "input"))
      (node (ref "U$7") (pin "SLP") (pinfunction "SLEEP_SLP") (pintype "input"))
    )
    (net (code "125") (name "VCC") (class "Default")
      (node (ref "JP11") (pin "3") (pinfunction "3_3") (pintype "passive"))
      (node (ref "JP15") (pin "5") (pinfunction "5_5") (pintype "passive"))
      (node (ref "R18") (pin "1") (pinfunction "1_1") (pintype "passive"))
      (node (ref "R19") (pin "1") (pinfunction "1_1") (pintype "passive"))
      (node (ref "R2") (pin "1") (pinfunction "1_1") (pintype "passive"))
      (node (ref "RN6") (pin "5") (pinfunction "2_5") (pintype "passive"))
      (node (ref "RX_LED") (pin "A") (pinfunction "A_A") (pintype "passive"))
      (node (ref "SER1") (pin "2") (pinfunction "2_2") (pintype "passive"))
      (node (ref "SER2") (pin "2") (pinfunction "2_2") (pintype "passive"))
      (node (ref "SJ1") (pin "1") (pinfunction "1_1") (pintype "passive"))
      (node (ref "SJ2") (pin "1") (pinfunction "1_1") (pintype "passive"))
      (node (ref "SJ3") (pin "1") (pinfunction "1_1") (pintype "passive"))
      (node (ref "SJ4") (pin "1") (pinfunction "1_1") (pintype "passive"))
      (node (ref "SJ5") (pin "1") (pinfunction "1_1") (pintype "passive"))
      (node (ref "SJ6") (pin "1") (pinfunction "1_1") (pintype "passive"))
      (node (ref "SJ7") (pin "1") (pinfunction "1_1") (pintype "passive"))
      (node (ref "SJ8") (pin "1") (pinfunction "1_1") (pintype "passive"))
      (node (ref "SJ9") (pin "1") (pinfunction "1_1") (pintype "passive"))
      (node (ref "TFT") (pin "3") (pinfunction "3_3") (pintype "passive"))
      (node (ref "TX_LED") (pin "A") (pinfunction "A_A") (pintype "passive"))
      (node (ref "U$1") (pin "VDD") (pinfunction "VDD_VDD") (pintype "power_in"))
      (node (ref "U$6") (pin "VDD") (pinfunction "VDD_VDD") (pintype "power_in"))
      (node (ref "U$7") (pin "VDD") (pinfunction "VDD_VDD") (pintype "power_in"))
      (node (ref "U1") (pin "5V@0") (pinfunction "5V_5V@0") (pintype "power_in"))
      (node (ref "U1") (pin "5V@1") (pinfunction "5V_5V@1") (pintype "power_in"))
      (node (ref "U1") (pin "5V@2") (pinfunction "5V_5V@2") (pintype "power_in"))
    )
    (net (code "126") (name "unconnected-(RN6-Pad1)") (class "Default")
      (node (ref "RN6") (pin "1") (pinfunction "1_1") (pintype "passive"))
    )
    (net (code "127") (name "unconnected-(RN6A-2-Pad8)") (class "Default")
      (node (ref "RN6") (pin "8") (pinfunction "2_8") (pintype "passive"))
    )
    (net (code "128") (name "unconnected-(TFT-Pad2)") (class "Default")
      (node (ref "TFT") (pin "2") (pinfunction "2_2") (pintype "passive"))
    )
    (net (code "129") (name "unconnected-(TFT-Pad4)") (class "Default")
      (node (ref "TFT") (pin "4") (pinfunction "4_4") (pintype "passive"))
    )
    (net (code "130") (name "unconnected-(TFT-Pad5)") (class "Default")
      (node (ref "TFT") (pin "5") (pinfunction "5_5") (pintype "passive"))
    )
    (net (code "131") (name "unconnected-(TFT-Pad6)") (class "Default")
      (node (ref "TFT") (pin "6") (pinfunction "6_6") (pintype "passive"))
    )
    (net (code "132") (name "unconnected-(TFT-Pad8)") (class "Default")
      (node (ref "TFT") (pin "8") (pinfunction "8_8") (pintype "passive"))
    )
    (net (code "133") (name "unconnected-(TFT-Pad10)") (class "Default")
      (node (ref "TFT") (pin "10") (pinfunction "10_10") (pintype "passive"))
    )
    (net (code "134") (name "unconnected-(TFT-Pad12)") (class "Default")
      (node (ref "TFT") (pin "12") (pinfunction "12_12") (pintype "passive"))
    )
    (net (code "135") (name "unconnected-(TFT-Pad14)") (class "Default")
      (node (ref "TFT") (pin "14") (pinfunction "14_14") (pintype "passive"))
    )
    (net (code "136") (name "unconnected-(TFT-Pad16)") (class "Default")
      (node (ref "TFT") (pin "16") (pinfunction "16_16") (pintype "passive"))
    )
    (net (code "137") (name "unconnected-(TFT-Pad24)") (class "Default")
      (node (ref "TFT") (pin "24") (pinfunction "24_24") (pintype "passive"))
    )
    (net (code "138") (name "unconnected-(TFT-Pad31)") (class "Default")
      (node (ref "TFT") (pin "31") (pinfunction "31_31") (pintype "passive"))
    )
    (net (code "139") (name "unconnected-(TFT-Pad35)") (class "Default")
      (node (ref "TFT") (pin "35") (pinfunction "35_35") (pintype "passive"))
    )
    (net (code "140") (name "unconnected-(TFT-Pad38)") (class "Default")
      (node (ref "TFT") (pin "38") (pinfunction "38_38") (pintype "passive"))
    )
    (net (code "141") (name "unconnected-(TFT-Pad39)") (class "Default")
      (node (ref "TFT") (pin "39") (pinfunction "39_39") (pintype "passive"))
    )
    (net (code "142") (name "unconnected-(TFT-Pad40)") (class "Default")
      (node (ref "TFT") (pin "40") (pinfunction "40_40") (pintype "passive"))
    )
  )
)
